# simplefoc-mini-native-power.net
KiCad netlist of a schematic drawn in Altium Designer
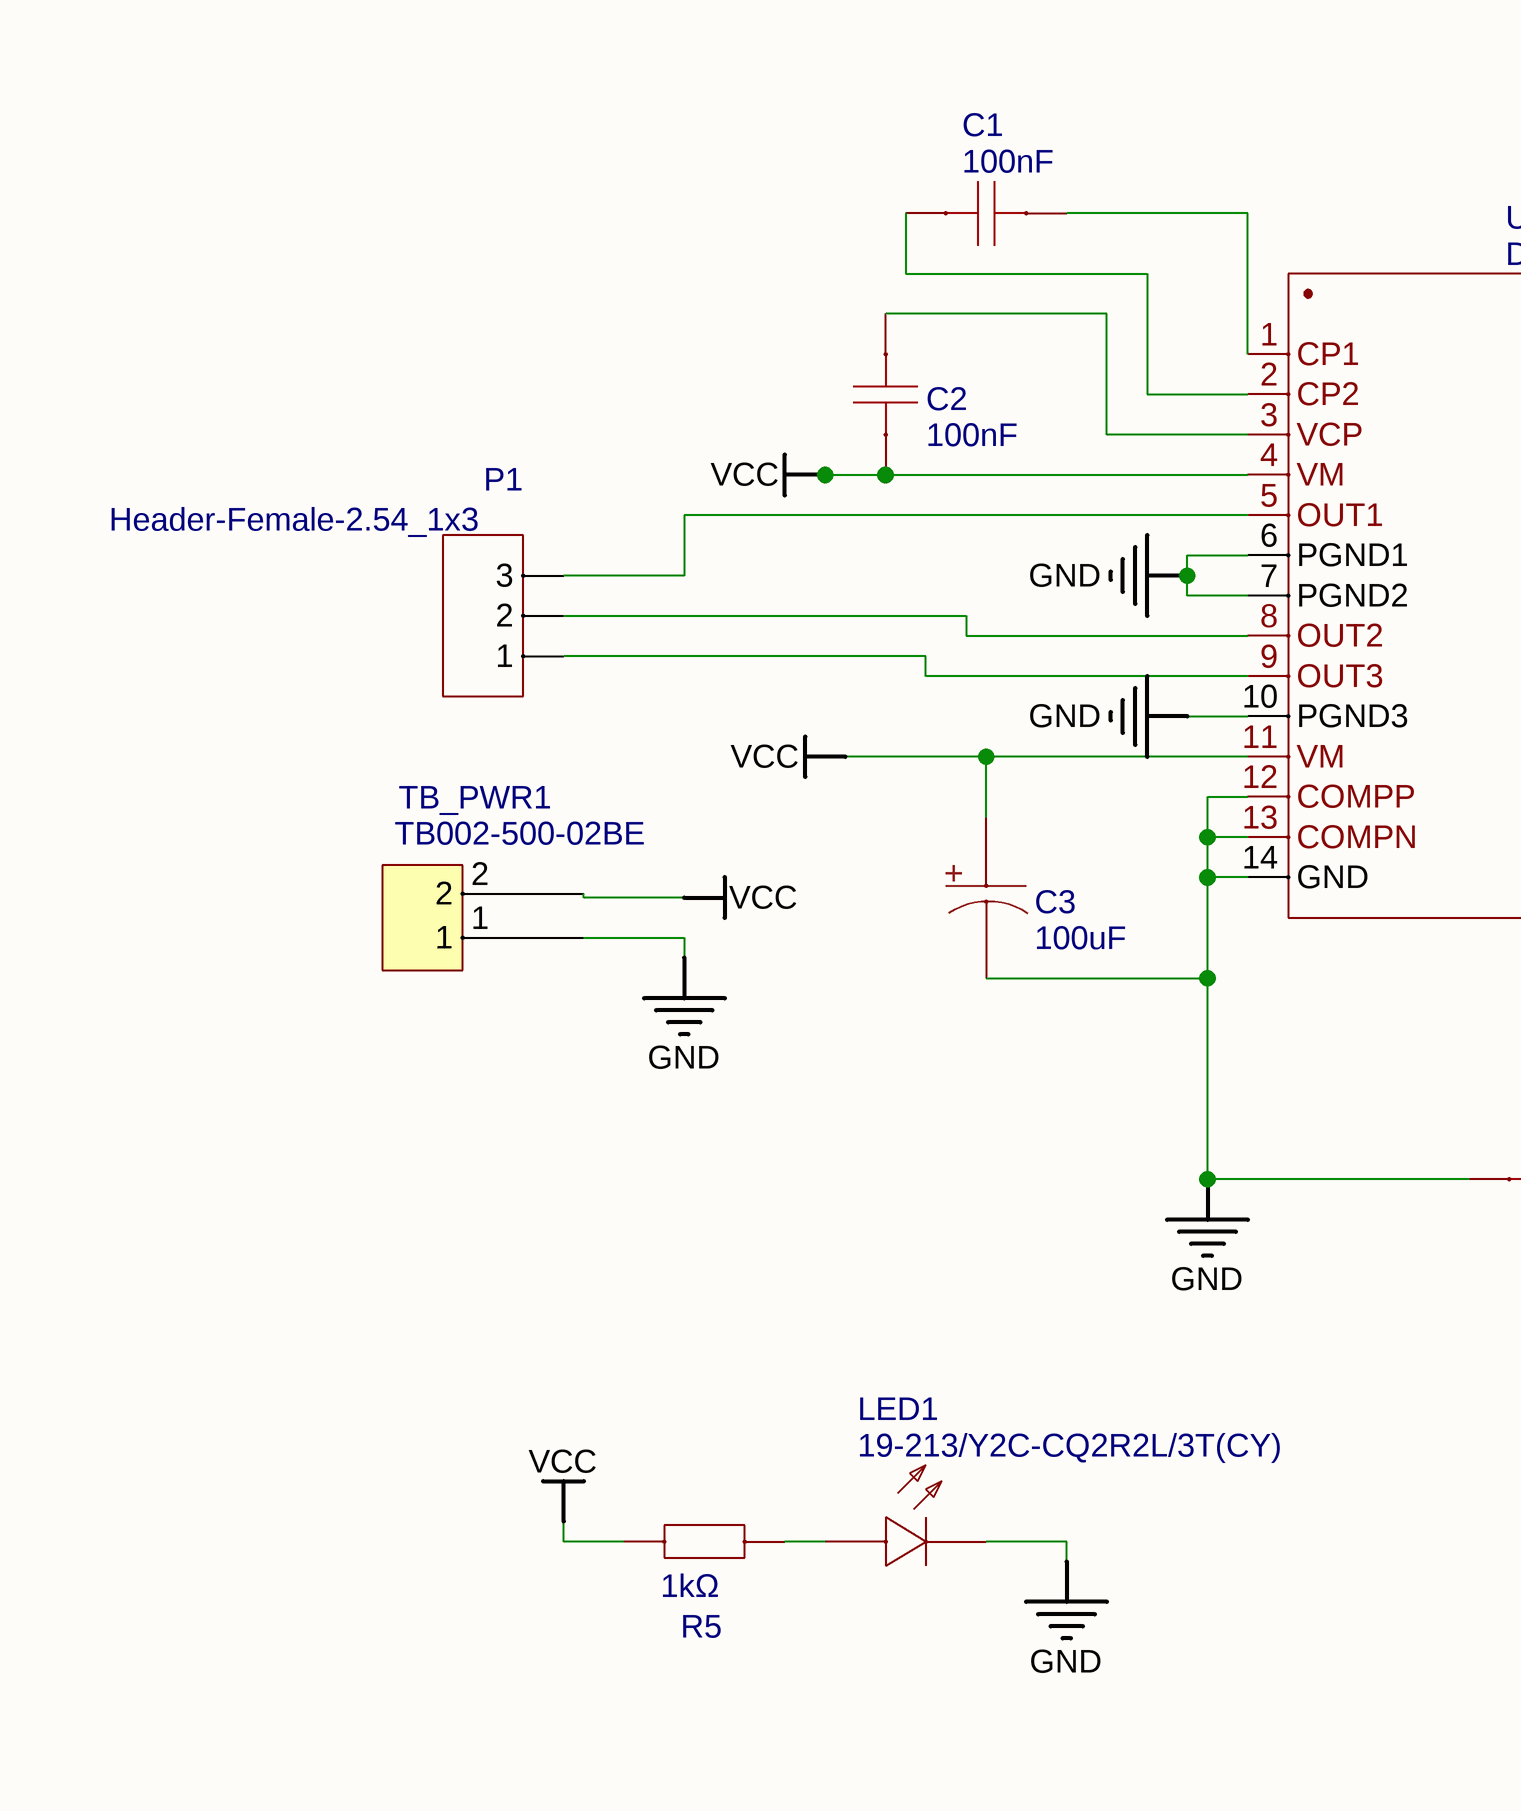
[diagram p0: simplefoc-mini-native-power.SchDoc, left]
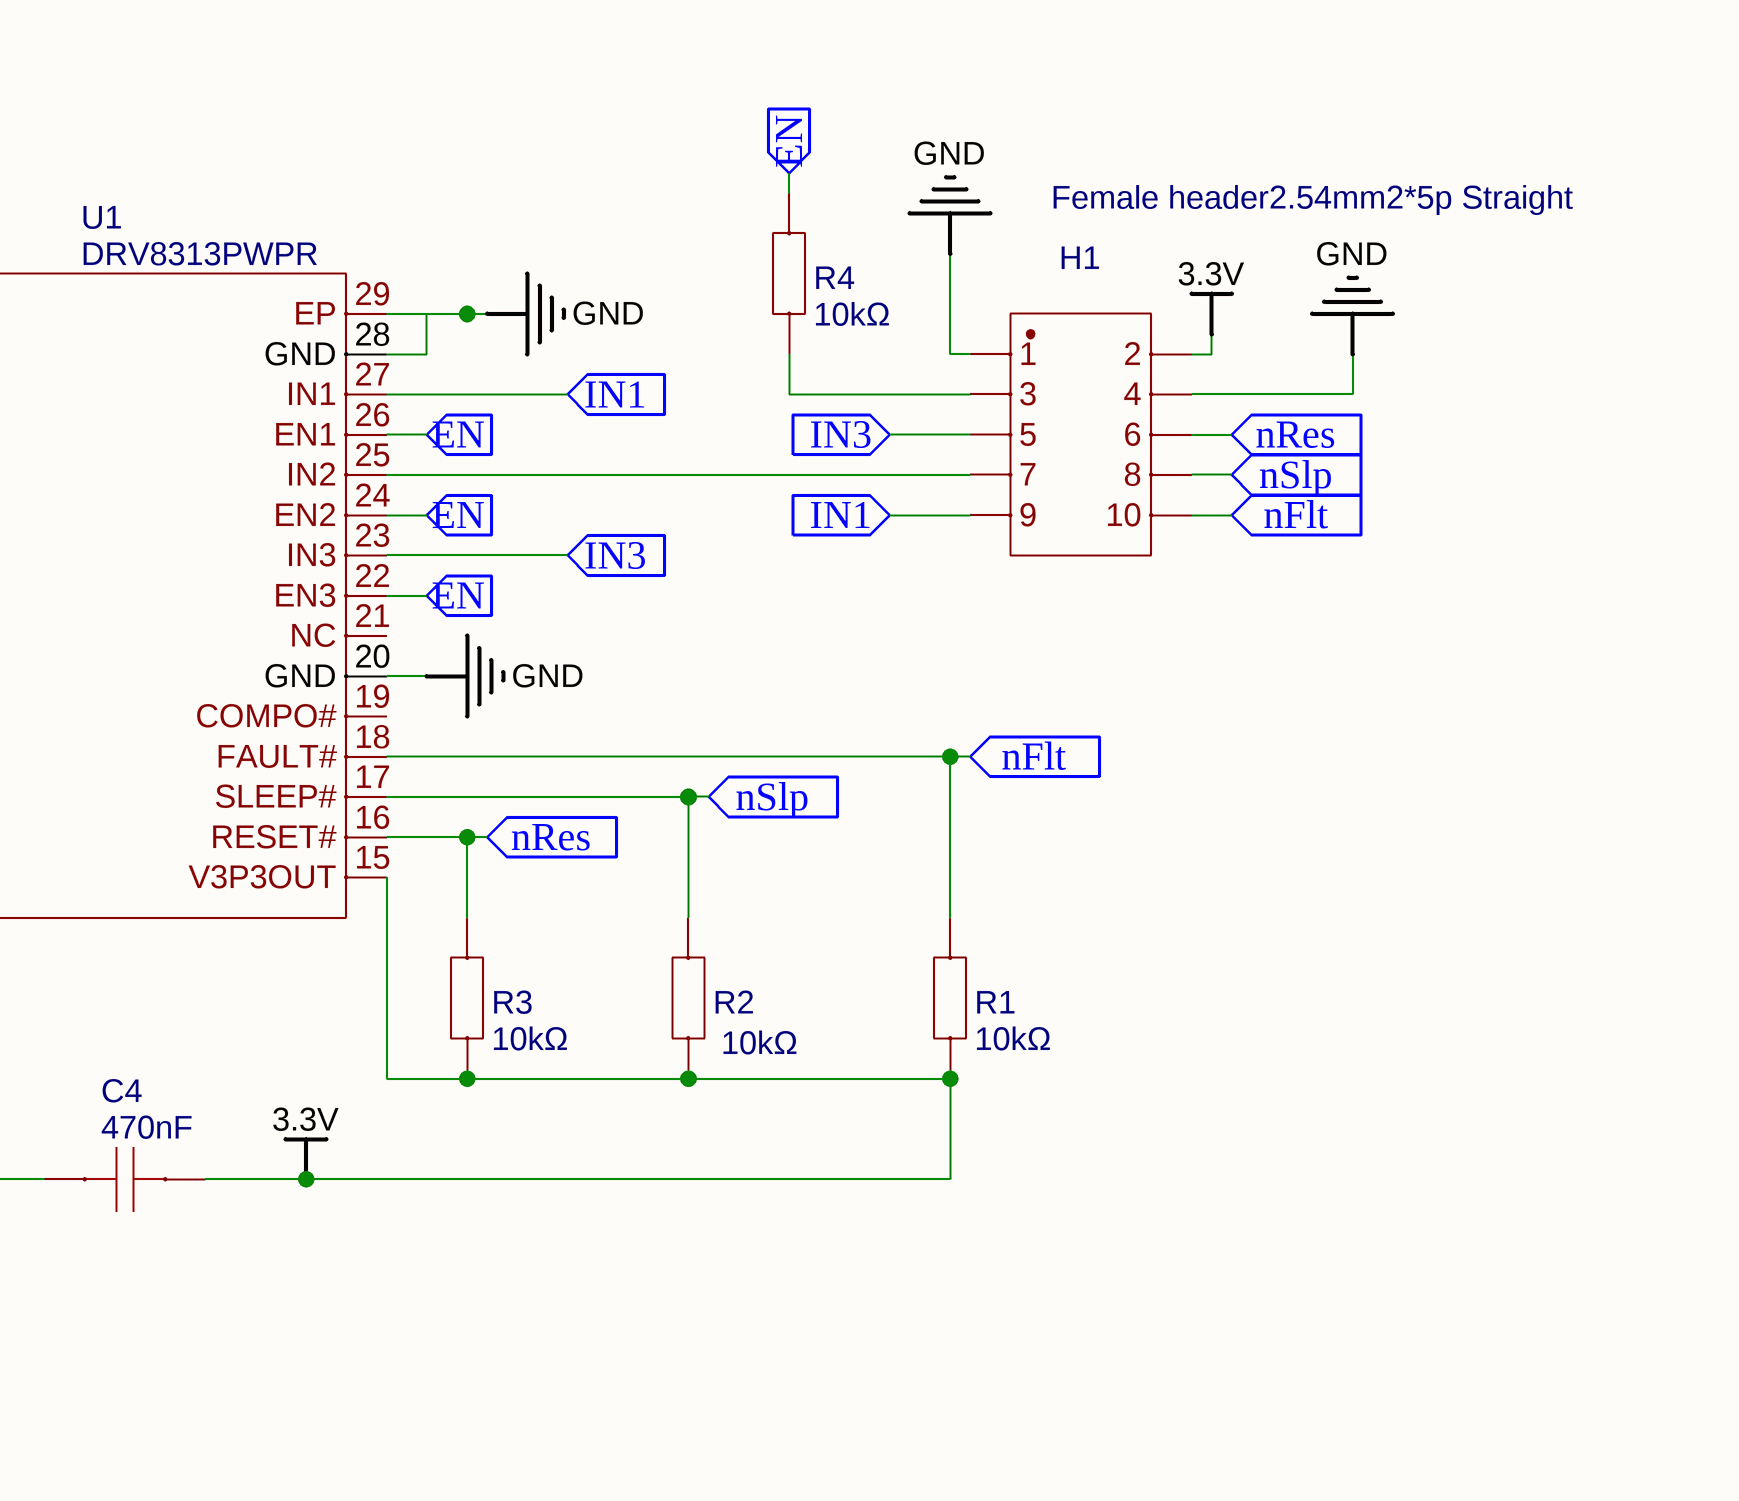
[diagram p1: simplefoc-mini-native-power.SchDoc, right]

(export (version "E")
  (design (tool "Eeschema 10.0.6"))
  (components
    (comp (ref "C1") (value "100nF") (libsource (lib "") (part "root_0_100nF__1")))
    (comp (ref "C2") (value "100nF") (libsource (lib "altium-import") (part "root_0_100nF_")))
    (comp (ref "C3") (value "100uF") (libsource (lib "altium-import") (part "root_0_100uF_")))
    (comp (ref "C4") (value "470nF") (libsource (lib "altium-import") (part "root_0_470nF_")))
    (comp (ref "H1")
      (value "Female header2.54mm2*5p Straight")
      (libsource (lib "altium-import") (part "root_0_Female header2.54mm2*5p Straight_"))
    )
    (comp (ref "LED1")
      (value "19-213/Y2C-CQ2R2L/3T(CY)")
      (libsource (lib "altium-import") (part "root_0_19-213/Y2C-CQ2R2L/3T(CY)_"))
    )
    (comp (ref "P1")
      (value "Header-Female-2.54_1x3")
      (libsource (lib "altium-import") (part "root_0_Header-Female-2.54_1x3_"))
    )
    (comp (ref "R1") (value "10kΩ") (libsource (lib "altium-import") (part "root_0_10kΩ_")))
    (comp (ref "R2") (value "10kΩ") (libsource (lib "altium-import") (part "root_0_10kΩ_")))
    (comp (ref "R3") (value "10kΩ") (libsource (lib "altium-import") (part "root_0_10kΩ_")))
    (comp (ref "R4") (value "10kΩ") (libsource (lib "altium-import") (part "root_0_10kΩ_")))
    (comp (ref "R5") (value "1kΩ") (libsource (lib "altium-import") (part "root_0_1kΩ_")))
    (comp (ref "TB_PWR1")
      (value "TB002-500-02BE")
      (libsource (lib "altium-import") (part "root_0_TB002-500-02BE_"))
    )
    (comp (ref "U1") (value "DRV8313PWPR") (libsource (lib "altium-import") (part "root_0_DRV8313PWPR_")))
  )
  (nets
    (net (code "1") (name "/EN") (class "Default")
      (node (ref "R4") (pin "2") (pinfunction "2_2") (pintype "passive"))
      (node (ref "U1") (pin "22") (pinfunction "EN3_22") (pintype "passive"))
      (node (ref "U1") (pin "24") (pinfunction "EN2_24") (pintype "passive"))
      (node (ref "U1") (pin "26") (pinfunction "EN1_26") (pintype "passive"))
    )
    (net (code "2") (name "/IN1") (class "Default")
      (node (ref "H1") (pin "9") (pinfunction "9_9") (pintype "passive"))
      (node (ref "U1") (pin "27") (pinfunction "IN1_27") (pintype "passive"))
    )
    (net (code "3") (name "/IN3") (class "Default")
      (node (ref "H1") (pin "5") (pinfunction "5_5") (pintype "passive"))
      (node (ref "U1") (pin "23") (pinfunction "IN3_23") (pintype "passive"))
    )
    (net (code "4") (name "/nFlt") (class "Default")
      (node (ref "H1") (pin "10") (pinfunction "10_10") (pintype "passive"))
      (node (ref "R1") (pin "2") (pinfunction "2_2") (pintype "passive"))
      (node (ref "U1") (pin "18") (pinfunction "FAULT#_18") (pintype "passive"))
    )
    (net (code "5") (name "/nRes") (class "Default")
      (node (ref "H1") (pin "6") (pinfunction "6_6") (pintype "passive"))
      (node (ref "R3") (pin "2") (pinfunction "2_2") (pintype "passive"))
      (node (ref "U1") (pin "16") (pinfunction "RESET#_16") (pintype "passive"))
    )
    (net (code "6") (name "/nSlp") (class "Default")
      (node (ref "H1") (pin "8") (pinfunction "8_8") (pintype "passive"))
      (node (ref "R2") (pin "2") (pinfunction "2_2") (pintype "passive"))
      (node (ref "U1") (pin "17") (pinfunction "SLEEP#_17") (pintype "passive"))
    )
    (net (code "7") (name "3.3V") (class "Default")
      (node (ref "C4") (pin "2") (pinfunction "2_2") (pintype "passive"))
      (node (ref "H1") (pin "2") (pinfunction "2_2") (pintype "passive"))
      (node (ref "R1") (pin "1") (pinfunction "1_1") (pintype "passive"))
      (node (ref "R2") (pin "1") (pinfunction "1_1") (pintype "passive"))
      (node (ref "R3") (pin "1") (pinfunction "1_1") (pintype "passive"))
      (node (ref "U1") (pin "15") (pinfunction "V3P3OUT_15") (pintype "passive"))
    )
    (net (code "8") (name "GND") (class "Default")
      (node (ref "C3") (pin "2") (pinfunction "2_2") (pintype "passive"))
      (node (ref "C4") (pin "1") (pinfunction "1_1") (pintype "passive"))
      (node (ref "H1") (pin "1") (pinfunction "1_1") (pintype "passive"))
      (node (ref "H1") (pin "4") (pinfunction "4_4") (pintype "passive"))
      (node (ref "LED1") (pin "2") (pinfunction "C_2") (pintype "passive"))
      (node (ref "TB_PWR1") (pin "1") (pinfunction "1_1") (pintype "passive"))
      (node (ref "U1") (pin "10") (pinfunction "PGND3_10") (pintype "passive"))
      (node (ref "U1") (pin "12") (pinfunction "COMPP_12") (pintype "passive"))
      (node (ref "U1") (pin "13") (pinfunction "COMPN_13") (pintype "passive"))
      (node (ref "U1") (pin "14") (pinfunction "GND_14") (pintype "passive"))
      (node (ref "U1") (pin "20") (pinfunction "GND_20") (pintype "passive"))
      (node (ref "U1") (pin "28") (pinfunction "GND_28") (pintype "passive"))
      (node (ref "U1") (pin "29") (pinfunction "EP_29") (pintype "passive"))
      (node (ref "U1") (pin "6") (pinfunction "PGND1_6") (pintype "passive"))
      (node (ref "U1") (pin "7") (pinfunction "PGND2_7") (pintype "passive"))
    )
    (net (code "9") (name "Net-(H1-Pad3)") (class "Default")
      (node (ref "H1") (pin "3") (pinfunction "3_3") (pintype "passive"))
      (node (ref "R4") (pin "1") (pinfunction "1_1") (pintype "passive"))
    )
    (net (code "10") (name "Net-(LED1-A)") (class "Default")
      (node (ref "LED1") (pin "1") (pinfunction "A_1") (pintype "passive"))
      (node (ref "R5") (pin "2") (pinfunction "2_2") (pintype "passive"))
    )
    (net (code "11") (name "Net-(U1-CP1)") (class "Default")
      (node (ref "C1") (pin "2") (pinfunction "2_2") (pintype "passive"))
      (node (ref "U1") (pin "1") (pinfunction "CP1_1") (pintype "passive"))
    )
    (net (code "12") (name "Net-(U1-CP2)") (class "Default")
      (node (ref "C1") (pin "1") (pinfunction "1_1") (pintype "passive"))
      (node (ref "U1") (pin "2") (pinfunction "CP2_2") (pintype "passive"))
    )
    (net (code "13") (name "Net-(U1-IN2)") (class "Default")
      (node (ref "H1") (pin "7") (pinfunction "7_7") (pintype "passive"))
      (node (ref "U1") (pin "25") (pinfunction "IN2_25") (pintype "passive"))
    )
    (net (code "14") (name "Net-(U1-OUT1)") (class "Default")
      (node (ref "P1") (pin "3") (pinfunction "3_3") (pintype "passive"))
      (node (ref "U1") (pin "5") (pinfunction "OUT1_5") (pintype "passive"))
    )
    (net (code "15") (name "Net-(U1-OUT2)") (class "Default")
      (node (ref "P1") (pin "2") (pinfunction "2_2") (pintype "passive"))
      (node (ref "U1") (pin "8") (pinfunction "OUT2_8") (pintype "passive"))
    )
    (net (code "16") (name "Net-(U1-OUT3)") (class "Default")
      (node (ref "P1") (pin "1") (pinfunction "1_1") (pintype "passive"))
      (node (ref "U1") (pin "9") (pinfunction "OUT3_9") (pintype "passive"))
    )
    (net (code "17") (name "Net-(U1-VCP)") (class "Default")
      (node (ref "C2") (pin "2") (pinfunction "2_2") (pintype "passive"))
      (node (ref "U1") (pin "3") (pinfunction "VCP_3") (pintype "passive"))
    )
    (net (code "18") (name "VCC") (class "Default")
      (node (ref "C2") (pin "1") (pinfunction "1_1") (pintype "passive"))
      (node (ref "C3") (pin "1") (pinfunction "1_1") (pintype "passive"))
      (node (ref "R5") (pin "1") (pinfunction "1_1") (pintype "passive"))
      (node (ref "TB_PWR1") (pin "2") (pinfunction "2_2") (pintype "passive"))
      (node (ref "U1") (pin "11") (pinfunction "VM_11") (pintype "passive"))
      (node (ref "U1") (pin "4") (pinfunction "VM_4") (pintype "passive"))
    )
    (net (code "19") (name "unconnected-(U1-COMPO#-Pad19)") (class "Default")
      (node (ref "U1") (pin "19") (pinfunction "COMPO#_19") (pintype "passive"))
    )
    (net (code "20") (name "unconnected-(U1-NC-Pad21)") (class "Default")
      (node (ref "U1") (pin "21") (pinfunction "NC_21") (pintype "passive"))
    )
  )
)
